# MB1115_TOP.net
KiCad netlist of a schematic drawn in Altium Designer
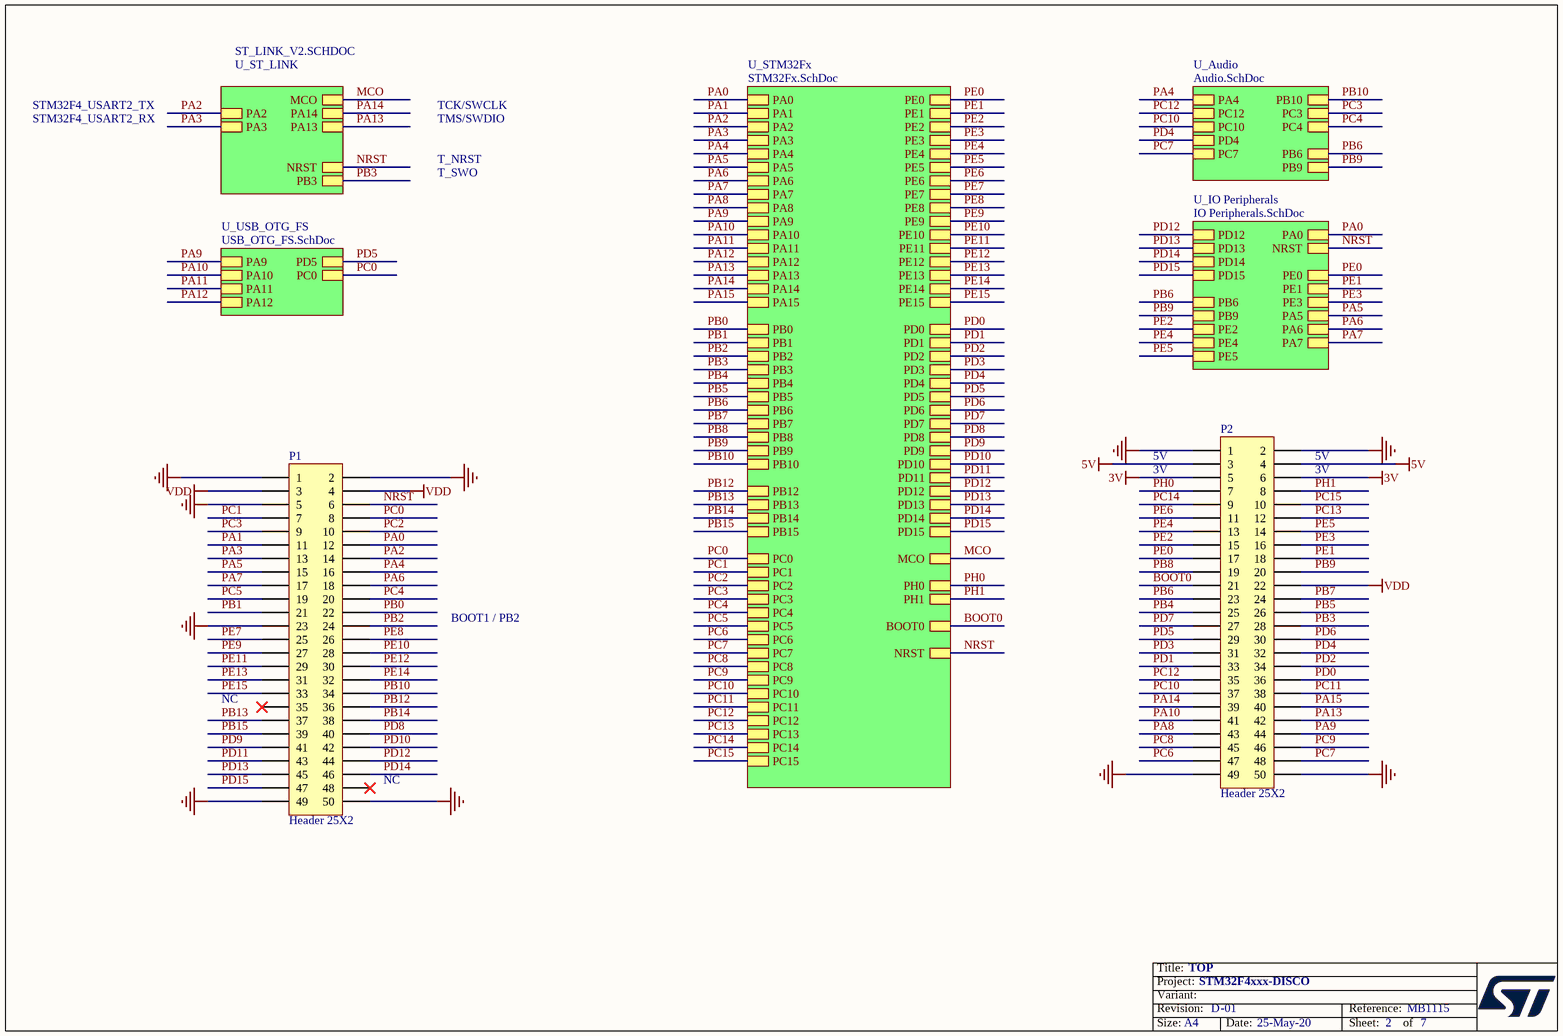
[diagram p0: MB1115_TOP.SchDoc]

(export (version "E")
  (design (tool "Eeschema 10.0.6"))
  (components
    (comp (ref "P1")
      (value "Header 25X2")
      (footprint "HDR2X25 (Primary)")
      (description "Header, 25-Pin, Dual row")
      (fields (field (name "PUBLISHER") "Altium Limited"))
      (libsource (lib "Miscellaneous Connectors") (part "Header 25X2"))
    )
    (comp (ref "P2")
      (value "Header 25X2")
      (footprint "HDR2X25 (Primary)")
      (description "Header, 25-Pin, Dual row")
      (fields (field (name "PUBLISHER") "Altium Limited"))
      (libsource (lib "Miscellaneous Connectors") (part "Header 25X2"))
    )
  )
  (nets
    (net (code "1") (name "/BOOT0") (class "Default")
      (node (ref "P2") (pin "21") (pinfunction "21_21") (pintype "passive"))
    )
    (net (code "3") (name "/NRST") (class "Default")
      (node (ref "P1") (pin "6") (pinfunction "6_6") (pintype "passive"))
    )
    (net (code "4") (name "/PA0") (class "Default")
      (node (ref "P1") (pin "12") (pinfunction "12_12") (pintype "passive"))
    )
    (net (code "5") (name "/PA1") (class "Default")
      (node (ref "P1") (pin "11") (pinfunction "11_11") (pintype "passive"))
    )
    (net (code "6") (name "/PA2") (class "Default")
      (node (ref "P1") (pin "14") (pinfunction "14_14") (pintype "passive"))
    )
    (net (code "7") (name "/PA3") (class "Default")
      (node (ref "P1") (pin "13") (pinfunction "13_13") (pintype "passive"))
    )
    (net (code "8") (name "/PA4") (class "Default")
      (node (ref "P1") (pin "16") (pinfunction "16_16") (pintype "passive"))
    )
    (net (code "9") (name "/PA5") (class "Default")
      (node (ref "P1") (pin "15") (pinfunction "15_15") (pintype "passive"))
    )
    (net (code "10") (name "/PA6") (class "Default")
      (node (ref "P1") (pin "18") (pinfunction "18_18") (pintype "passive"))
    )
    (net (code "11") (name "/PA7") (class "Default")
      (node (ref "P1") (pin "17") (pinfunction "17_17") (pintype "passive"))
    )
    (net (code "12") (name "/PA8") (class "Default")
      (node (ref "P2") (pin "43") (pinfunction "43_43") (pintype "passive"))
    )
    (net (code "13") (name "/PA9") (class "Default")
      (node (ref "P2") (pin "44") (pinfunction "44_44") (pintype "passive"))
    )
    (net (code "14") (name "/PA10") (class "Default")
      (node (ref "P2") (pin "41") (pinfunction "41_41") (pintype "passive"))
    )
    (net (code "17") (name "/PA13") (class "Default")
      (node (ref "P2") (pin "42") (pinfunction "42_42") (pintype "passive"))
    )
    (net (code "18") (name "/PA14") (class "Default")
      (node (ref "P2") (pin "39") (pinfunction "39_39") (pintype "passive"))
    )
    (net (code "19") (name "/PA15") (class "Default")
      (node (ref "P2") (pin "40") (pinfunction "40_40") (pintype "passive"))
    )
    (net (code "20") (name "/PB0") (class "Default")
      (node (ref "P1") (pin "22") (pinfunction "22_22") (pintype "passive"))
    )
    (net (code "21") (name "/PB1") (class "Default")
      (node (ref "P1") (pin "21") (pinfunction "21_21") (pintype "passive"))
    )
    (net (code "22") (name "/PB2") (class "Default")
      (node (ref "P1") (pin "24") (pinfunction "24_24") (pintype "passive"))
    )
    (net (code "23") (name "/PB3") (class "Default")
      (node (ref "P2") (pin "28") (pinfunction "28_28") (pintype "passive"))
    )
    (net (code "24") (name "/PB4") (class "Default")
      (node (ref "P2") (pin "25") (pinfunction "25_25") (pintype "passive"))
    )
    (net (code "25") (name "/PB5") (class "Default")
      (node (ref "P2") (pin "26") (pinfunction "26_26") (pintype "passive"))
    )
    (net (code "26") (name "/PB6") (class "Default")
      (node (ref "P2") (pin "23") (pinfunction "23_23") (pintype "passive"))
    )
    (net (code "27") (name "/PB7") (class "Default")
      (node (ref "P2") (pin "24") (pinfunction "24_24") (pintype "passive"))
    )
    (net (code "28") (name "/PB8") (class "Default")
      (node (ref "P2") (pin "19") (pinfunction "19_19") (pintype "passive"))
    )
    (net (code "29") (name "/PB9") (class "Default")
      (node (ref "P2") (pin "20") (pinfunction "20_20") (pintype "passive"))
    )
    (net (code "30") (name "/PB10") (class "Default")
      (node (ref "P1") (pin "34") (pinfunction "34_34") (pintype "passive"))
    )
    (net (code "31") (name "/PB12") (class "Default")
      (node (ref "P1") (pin "36") (pinfunction "36_36") (pintype "passive"))
    )
    (net (code "32") (name "/PB13") (class "Default")
      (node (ref "P1") (pin "37") (pinfunction "37_37") (pintype "passive"))
    )
    (net (code "33") (name "/PB14") (class "Default")
      (node (ref "P1") (pin "38") (pinfunction "38_38") (pintype "passive"))
    )
    (net (code "34") (name "/PB15") (class "Default")
      (node (ref "P1") (pin "39") (pinfunction "39_39") (pintype "passive"))
    )
    (net (code "35") (name "/PC0") (class "Default")
      (node (ref "P1") (pin "8") (pinfunction "8_8") (pintype "passive"))
    )
    (net (code "36") (name "/PC1") (class "Default")
      (node (ref "P1") (pin "7") (pinfunction "7_7") (pintype "passive"))
    )
    (net (code "37") (name "/PC2") (class "Default")
      (node (ref "P1") (pin "10") (pinfunction "10_10") (pintype "passive"))
    )
    (net (code "38") (name "/PC3") (class "Default")
      (node (ref "P1") (pin "9") (pinfunction "9_9") (pintype "passive"))
    )
    (net (code "39") (name "/PC4") (class "Default")
      (node (ref "P1") (pin "20") (pinfunction "20_20") (pintype "passive"))
    )
    (net (code "40") (name "/PC5") (class "Default")
      (node (ref "P1") (pin "19") (pinfunction "19_19") (pintype "passive"))
    )
    (net (code "41") (name "/PC6") (class "Default")
      (node (ref "P2") (pin "47") (pinfunction "47_47") (pintype "passive"))
    )
    (net (code "42") (name "/PC7") (class "Default")
      (node (ref "P2") (pin "48") (pinfunction "48_48") (pintype "passive"))
    )
    (net (code "43") (name "/PC8") (class "Default")
      (node (ref "P2") (pin "45") (pinfunction "45_45") (pintype "passive"))
    )
    (net (code "44") (name "/PC9") (class "Default")
      (node (ref "P2") (pin "46") (pinfunction "46_46") (pintype "passive"))
    )
    (net (code "45") (name "/PC10") (class "Default")
      (node (ref "P2") (pin "37") (pinfunction "37_37") (pintype "passive"))
    )
    (net (code "46") (name "/PC11") (class "Default")
      (node (ref "P2") (pin "38") (pinfunction "38_38") (pintype "passive"))
    )
    (net (code "47") (name "/PC12") (class "Default")
      (node (ref "P2") (pin "35") (pinfunction "35_35") (pintype "passive"))
    )
    (net (code "48") (name "/PC13") (class "Default")
      (node (ref "P2") (pin "12") (pinfunction "12_12") (pintype "passive"))
    )
    (net (code "49") (name "/PC14") (class "Default")
      (node (ref "P2") (pin "9") (pinfunction "9_9") (pintype "passive"))
    )
    (net (code "50") (name "/PC15") (class "Default")
      (node (ref "P2") (pin "10") (pinfunction "10_10") (pintype "passive"))
    )
    (net (code "51") (name "/PD0") (class "Default")
      (node (ref "P2") (pin "36") (pinfunction "36_36") (pintype "passive"))
    )
    (net (code "52") (name "/PD1") (class "Default")
      (node (ref "P2") (pin "33") (pinfunction "33_33") (pintype "passive"))
    )
    (net (code "53") (name "/PD2") (class "Default")
      (node (ref "P2") (pin "34") (pinfunction "34_34") (pintype "passive"))
    )
    (net (code "54") (name "/PD3") (class "Default")
      (node (ref "P2") (pin "31") (pinfunction "31_31") (pintype "passive"))
    )
    (net (code "55") (name "/PD4") (class "Default")
      (node (ref "P2") (pin "32") (pinfunction "32_32") (pintype "passive"))
    )
    (net (code "56") (name "/PD5") (class "Default")
      (node (ref "P2") (pin "29") (pinfunction "29_29") (pintype "passive"))
    )
    (net (code "57") (name "/PD6") (class "Default")
      (node (ref "P2") (pin "30") (pinfunction "30_30") (pintype "passive"))
    )
    (net (code "58") (name "/PD7") (class "Default")
      (node (ref "P2") (pin "27") (pinfunction "27_27") (pintype "passive"))
    )
    (net (code "59") (name "/PD8") (class "Default")
      (node (ref "P1") (pin "40") (pinfunction "40_40") (pintype "passive"))
    )
    (net (code "60") (name "/PD9") (class "Default")
      (node (ref "P1") (pin "41") (pinfunction "41_41") (pintype "passive"))
    )
    (net (code "61") (name "/PD10") (class "Default")
      (node (ref "P1") (pin "42") (pinfunction "42_42") (pintype "passive"))
    )
    (net (code "62") (name "/PD11") (class "Default")
      (node (ref "P1") (pin "43") (pinfunction "43_43") (pintype "passive"))
    )
    (net (code "63") (name "/PD12") (class "Default")
      (node (ref "P1") (pin "44") (pinfunction "44_44") (pintype "passive"))
    )
    (net (code "64") (name "/PD13") (class "Default")
      (node (ref "P1") (pin "45") (pinfunction "45_45") (pintype "passive"))
    )
    (net (code "65") (name "/PD14") (class "Default")
      (node (ref "P1") (pin "46") (pinfunction "46_46") (pintype "passive"))
    )
    (net (code "66") (name "/PD15") (class "Default")
      (node (ref "P1") (pin "47") (pinfunction "47_47") (pintype "passive"))
    )
    (net (code "67") (name "/PE0") (class "Default")
      (node (ref "P2") (pin "17") (pinfunction "17_17") (pintype "passive"))
    )
    (net (code "68") (name "/PE1") (class "Default")
      (node (ref "P2") (pin "18") (pinfunction "18_18") (pintype "passive"))
    )
    (net (code "69") (name "/PE2") (class "Default")
      (node (ref "P2") (pin "15") (pinfunction "15_15") (pintype "passive"))
    )
    (net (code "70") (name "/PE3") (class "Default")
      (node (ref "P2") (pin "16") (pinfunction "16_16") (pintype "passive"))
    )
    (net (code "71") (name "/PE4") (class "Default")
      (node (ref "P2") (pin "13") (pinfunction "13_13") (pintype "passive"))
    )
    (net (code "72") (name "/PE5") (class "Default")
      (node (ref "P2") (pin "14") (pinfunction "14_14") (pintype "passive"))
    )
    (net (code "73") (name "/PE6") (class "Default")
      (node (ref "P2") (pin "11") (pinfunction "11_11") (pintype "passive"))
    )
    (net (code "74") (name "/PE7") (class "Default")
      (node (ref "P1") (pin "25") (pinfunction "25_25") (pintype "passive"))
    )
    (net (code "75") (name "/PE8") (class "Default")
      (node (ref "P1") (pin "26") (pinfunction "26_26") (pintype "passive"))
    )
    (net (code "76") (name "/PE9") (class "Default")
      (node (ref "P1") (pin "27") (pinfunction "27_27") (pintype "passive"))
    )
    (net (code "77") (name "/PE10") (class "Default")
      (node (ref "P1") (pin "28") (pinfunction "28_28") (pintype "passive"))
    )
    (net (code "78") (name "/PE11") (class "Default")
      (node (ref "P1") (pin "29") (pinfunction "29_29") (pintype "passive"))
    )
    (net (code "79") (name "/PE12") (class "Default")
      (node (ref "P1") (pin "30") (pinfunction "30_30") (pintype "passive"))
    )
    (net (code "80") (name "/PE13") (class "Default")
      (node (ref "P1") (pin "31") (pinfunction "31_31") (pintype "passive"))
    )
    (net (code "81") (name "/PE14") (class "Default")
      (node (ref "P1") (pin "32") (pinfunction "32_32") (pintype "passive"))
    )
    (net (code "82") (name "/PE15") (class "Default")
      (node (ref "P1") (pin "33") (pinfunction "33_33") (pintype "passive"))
    )
    (net (code "83") (name "/PH0") (class "Default")
      (node (ref "P2") (pin "7") (pinfunction "7_7") (pintype "passive"))
    )
    (net (code "84") (name "/PH1") (class "Default")
      (node (ref "P2") (pin "8") (pinfunction "8_8") (pintype "passive"))
    )
    (net (code "85") (name "3V") (class "Default")
      (node (ref "P2") (pin "5") (pinfunction "5_5") (pintype "passive"))
      (node (ref "P2") (pin "6") (pinfunction "6_6") (pintype "passive"))
    )
    (net (code "86") (name "5V") (class "Default")
      (node (ref "P2") (pin "3") (pinfunction "3_3") (pintype "passive"))
      (node (ref "P2") (pin "4") (pinfunction "4_4") (pintype "passive"))
    )
    (net (code "87") (name "GND") (class "Default")
      (node (ref "P1") (pin "1") (pinfunction "1_1") (pintype "passive"))
      (node (ref "P1") (pin "2") (pinfunction "2_2") (pintype "passive"))
      (node (ref "P1") (pin "23") (pinfunction "23_23") (pintype "passive"))
      (node (ref "P1") (pin "49") (pinfunction "49_49") (pintype "passive"))
      (node (ref "P1") (pin "5") (pinfunction "5_5") (pintype "passive"))
      (node (ref "P1") (pin "50") (pinfunction "50_50") (pintype "passive"))
      (node (ref "P2") (pin "1") (pinfunction "1_1") (pintype "passive"))
      (node (ref "P2") (pin "2") (pinfunction "2_2") (pintype "passive"))
      (node (ref "P2") (pin "49") (pinfunction "49_49") (pintype "passive"))
      (node (ref "P2") (pin "50") (pinfunction "50_50") (pintype "passive"))
    )
    (net (code "88") (name "VDD") (class "Default")
      (node (ref "P1") (pin "3") (pinfunction "3_3") (pintype "passive"))
      (node (ref "P1") (pin "4") (pinfunction "4_4") (pintype "passive"))
      (node (ref "P2") (pin "22") (pinfunction "22_22") (pintype "passive"))
    )
    (net (code "89") (name "unconnected-(P1-Pad35)") (class "Default")
      (node (ref "P1") (pin "35") (pinfunction "35_35") (pintype "passive+no_connect"))
    )
    (net (code "90") (name "unconnected-(P1-Pad48)") (class "Default")
      (node (ref "P1") (pin "48") (pinfunction "48_48") (pintype "passive+no_connect"))
    )
  )
)
